# Digital_Output.net
KiCad netlist of a schematic drawn in Altium Designer
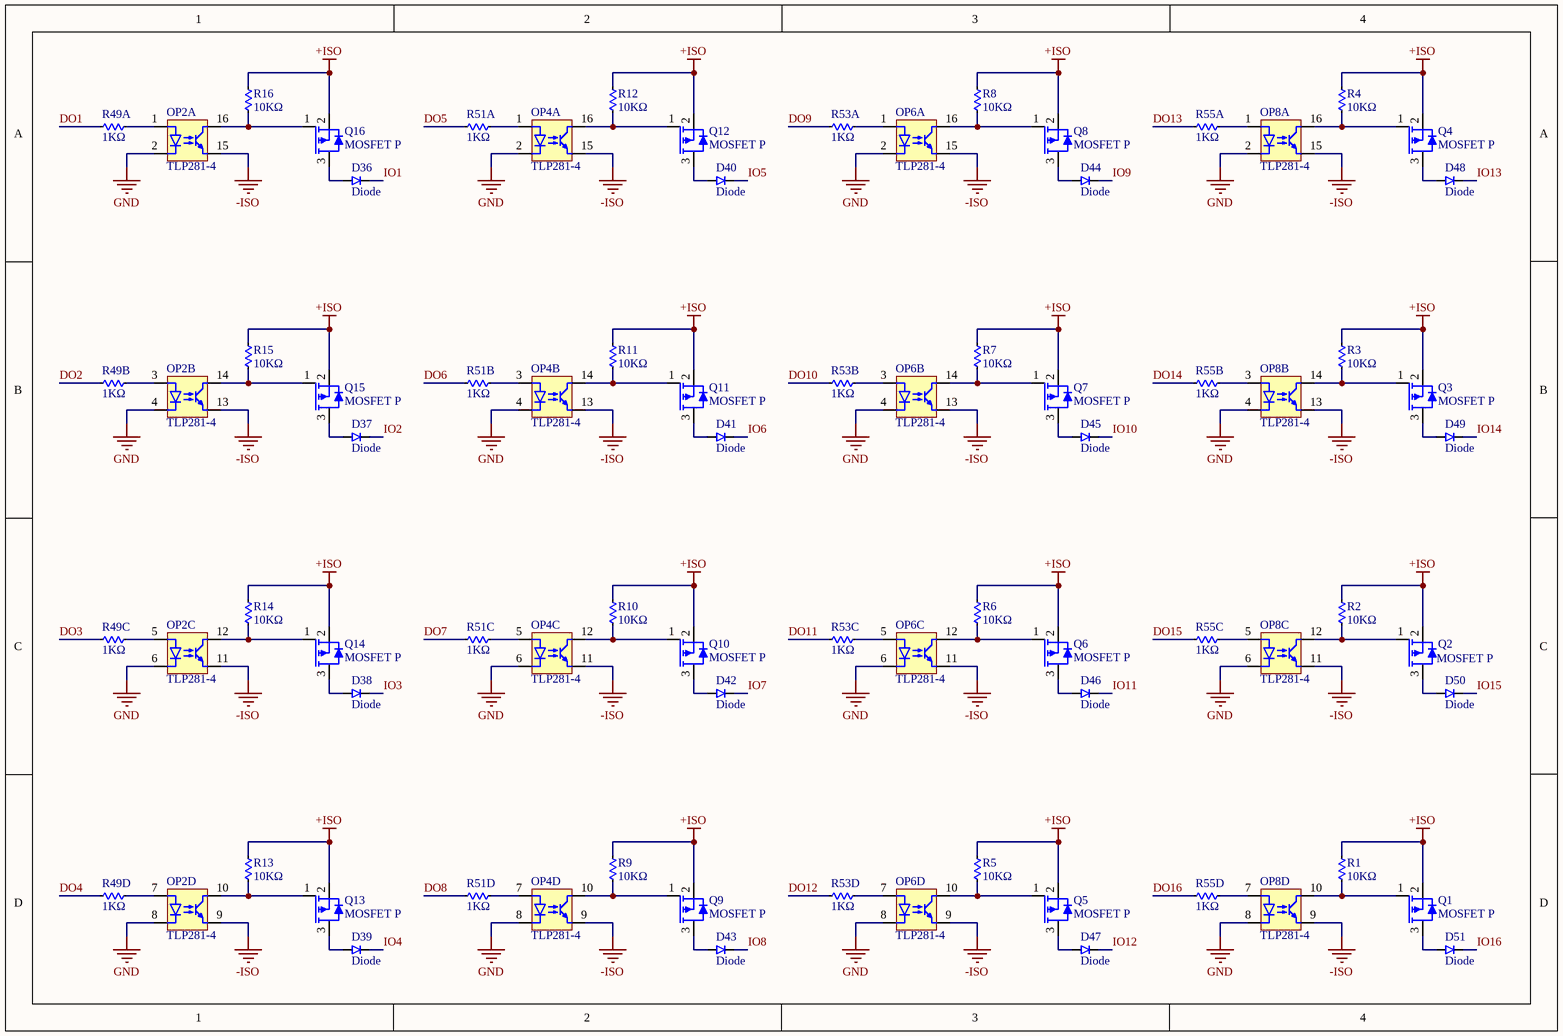
[diagram p0: Digital Output.SchDoc]

(export (version "E")
  (design (tool "Eeschema 10.0.6"))
  (components
    (comp (ref "D36") (value "Diode") (footprint "DIOMELF3515L") (libsource (lib "Shahnahad") (part "Diode")))
    (comp (ref "D37") (value "Diode") (footprint "DIOMELF3515L") (libsource (lib "Shahnahad") (part "Diode")))
    (comp (ref "D38") (value "Diode") (footprint "DIOMELF3515L") (libsource (lib "Shahnahad") (part "Diode")))
    (comp (ref "D39") (value "Diode") (footprint "DIOMELF3515L") (libsource (lib "Shahnahad") (part "Diode")))
    (comp (ref "D40") (value "Diode") (footprint "DIOMELF3515L") (libsource (lib "Shahnahad") (part "Diode")))
    (comp (ref "D41") (value "Diode") (footprint "DIOMELF3515L") (libsource (lib "Shahnahad") (part "Diode")))
    (comp (ref "D42") (value "Diode") (footprint "DIOMELF3515L") (libsource (lib "Shahnahad") (part "Diode")))
    (comp (ref "D43") (value "Diode") (footprint "DIOMELF3515L") (libsource (lib "Shahnahad") (part "Diode")))
    (comp (ref "D44") (value "Diode") (footprint "DIOMELF3515L") (libsource (lib "Shahnahad") (part "Diode")))
    (comp (ref "D45") (value "Diode") (footprint "DIOMELF3515L") (libsource (lib "Shahnahad") (part "Diode")))
    (comp (ref "D46") (value "Diode") (footprint "DIOMELF3515L") (libsource (lib "Shahnahad") (part "Diode")))
    (comp (ref "D47") (value "Diode") (footprint "DIOMELF3515L") (libsource (lib "Shahnahad") (part "Diode")))
    (comp (ref "D48") (value "Diode") (footprint "DIOMELF3515L") (libsource (lib "Shahnahad") (part "Diode")))
    (comp (ref "D49") (value "Diode") (footprint "DIOMELF3515L") (libsource (lib "Shahnahad") (part "Diode")))
    (comp (ref "D50") (value "Diode") (footprint "DIOMELF3515L") (libsource (lib "Shahnahad") (part "Diode")))
    (comp (ref "D51") (value "Diode") (footprint "DIOMELF3515L") (libsource (lib "Shahnahad") (part "Diode")))
    (comp (ref "OP2")
      (value "TLP281-4")
      (footprint "SO16 TOSHIBA OPTOCOUPLER")
      (libsource (lib "Shahnahad") (part "TLP281-4"))
    )
    (comp (ref "OP4")
      (value "TLP281-4")
      (footprint "SO16 TOSHIBA OPTOCOUPLER")
      (libsource (lib "Shahnahad") (part "TLP281-4"))
    )
    (comp (ref "OP6")
      (value "TLP281-4")
      (footprint "SO16 TOSHIBA OPTOCOUPLER")
      (libsource (lib "Shahnahad") (part "TLP281-4"))
    )
    (comp (ref "OP8")
      (value "TLP281-4")
      (footprint "SO16 TOSHIBA OPTOCOUPLER")
      (libsource (lib "Shahnahad") (part "TLP281-4"))
    )
    (comp (ref "Q1") (value "MOSFET P") (footprint "SOT23") (libsource (lib "Shahnahad") (part "MOSFET P")))
    (comp (ref "Q2") (value "MOSFET P") (footprint "SOT23") (libsource (lib "Shahnahad") (part "MOSFET P")))
    (comp (ref "Q3") (value "MOSFET P") (footprint "SOT23") (libsource (lib "Shahnahad") (part "MOSFET P")))
    (comp (ref "Q4") (value "MOSFET P") (footprint "SOT23") (libsource (lib "Shahnahad") (part "MOSFET P")))
    (comp (ref "Q5") (value "MOSFET P") (footprint "SOT23") (libsource (lib "Shahnahad") (part "MOSFET P")))
    (comp (ref "Q6") (value "MOSFET P") (footprint "SOT23") (libsource (lib "Shahnahad") (part "MOSFET P")))
    (comp (ref "Q7") (value "MOSFET P") (footprint "SOT23") (libsource (lib "Shahnahad") (part "MOSFET P")))
    (comp (ref "Q8") (value "MOSFET P") (footprint "SOT23") (libsource (lib "Shahnahad") (part "MOSFET P")))
    (comp (ref "Q9") (value "MOSFET P") (footprint "SOT23") (libsource (lib "Shahnahad") (part "MOSFET P")))
    (comp (ref "Q10") (value "MOSFET P") (footprint "SOT23") (libsource (lib "Shahnahad") (part "MOSFET P")))
    (comp (ref "Q11") (value "MOSFET P") (footprint "SOT23") (libsource (lib "Shahnahad") (part "MOSFET P")))
    (comp (ref "Q12") (value "MOSFET P") (footprint "SOT23") (libsource (lib "Shahnahad") (part "MOSFET P")))
    (comp (ref "Q13") (value "MOSFET P") (footprint "SOT23") (libsource (lib "Shahnahad") (part "MOSFET P")))
    (comp (ref "Q14") (value "MOSFET P") (footprint "SOT23") (libsource (lib "Shahnahad") (part "MOSFET P")))
    (comp (ref "Q15") (value "MOSFET P") (footprint "SOT23") (libsource (lib "Shahnahad") (part "MOSFET P")))
    (comp (ref "Q16") (value "MOSFET P") (footprint "SOT23") (libsource (lib "Shahnahad") (part "MOSFET P")))
    (comp (ref "R1") (value "10KΩ") (footprint "RES 0603 10K") (libsource (lib "Shahnahad") (part "RES 10K")))
    (comp (ref "R2") (value "10KΩ") (footprint "RES 0603 10K") (libsource (lib "Shahnahad") (part "RES 10K")))
    (comp (ref "R3") (value "10KΩ") (footprint "RES 0603 10K") (libsource (lib "Shahnahad") (part "RES 10K")))
    (comp (ref "R4") (value "10KΩ") (footprint "RES 0603 10K") (libsource (lib "Shahnahad") (part "RES 10K")))
    (comp (ref "R5") (value "10KΩ") (footprint "RES 0603 10K") (libsource (lib "Shahnahad") (part "RES 10K")))
    (comp (ref "R6") (value "10KΩ") (footprint "RES 0603 10K") (libsource (lib "Shahnahad") (part "RES 10K")))
    (comp (ref "R7") (value "10KΩ") (footprint "RES 0603 10K") (libsource (lib "Shahnahad") (part "RES 10K")))
    (comp (ref "R8") (value "10KΩ") (footprint "RES 0603 10K") (libsource (lib "Shahnahad") (part "RES 10K")))
    (comp (ref "R9") (value "10KΩ") (footprint "RES 0603 10K") (libsource (lib "Shahnahad") (part "RES 10K")))
    (comp (ref "R10")
      (value "10KΩ")
      (footprint "RES 0603 10K")
      (libsource (lib "Shahnahad") (part "RES 10K"))
    )
    (comp (ref "R11")
      (value "10KΩ")
      (footprint "RES 0603 10K")
      (libsource (lib "Shahnahad") (part "RES 10K"))
    )
    (comp (ref "R12")
      (value "10KΩ")
      (footprint "RES 0603 10K")
      (libsource (lib "Shahnahad") (part "RES 10K"))
    )
    (comp (ref "R13")
      (value "10KΩ")
      (footprint "RES 0603 10K")
      (libsource (lib "Shahnahad") (part "RES 10K"))
    )
    (comp (ref "R14")
      (value "10KΩ")
      (footprint "RES 0603 10K")
      (libsource (lib "Shahnahad") (part "RES 10K"))
    )
    (comp (ref "R15")
      (value "10KΩ")
      (footprint "RES 0603 10K")
      (libsource (lib "Shahnahad") (part "RES 10K"))
    )
    (comp (ref "R16")
      (value "10KΩ")
      (footprint "RES 0603 10K")
      (libsource (lib "Shahnahad") (part "RES 10K"))
    )
    (comp (ref "R49")
      (value "1KΩ")
      (footprint "RES ARRAY 4X0603 1K")
      (libsource (lib "Shahnahad") (part "RES ARRAY 1K"))
    )
    (comp (ref "R51")
      (value "1KΩ")
      (footprint "RES ARRAY 4X0603 1K")
      (libsource (lib "Shahnahad") (part "RES ARRAY 1K"))
    )
    (comp (ref "R53")
      (value "1KΩ")
      (footprint "RES ARRAY 4X0603 1K")
      (libsource (lib "Shahnahad") (part "RES ARRAY 1K"))
    )
    (comp (ref "R55")
      (value "1KΩ")
      (footprint "RES ARRAY 4X0603 1K")
      (libsource (lib "Shahnahad") (part "RES ARRAY 1K"))
    )
  )
  (nets
    (net (code "1") (name "+ISO") (class "Default")
      (node (ref "Q1") (pin "2") (pinfunction "S_2") (pintype "passive"))
      (node (ref "Q10") (pin "2") (pinfunction "S_2") (pintype "passive"))
      (node (ref "Q11") (pin "2") (pinfunction "S_2") (pintype "passive"))
      (node (ref "Q12") (pin "2") (pinfunction "S_2") (pintype "passive"))
      (node (ref "Q13") (pin "2") (pinfunction "S_2") (pintype "passive"))
      (node (ref "Q14") (pin "2") (pinfunction "S_2") (pintype "passive"))
      (node (ref "Q15") (pin "2") (pinfunction "S_2") (pintype "passive"))
      (node (ref "Q16") (pin "2") (pinfunction "S_2") (pintype "passive"))
      (node (ref "Q2") (pin "2") (pinfunction "S_2") (pintype "passive"))
      (node (ref "Q3") (pin "2") (pinfunction "S_2") (pintype "passive"))
      (node (ref "Q4") (pin "2") (pinfunction "S_2") (pintype "passive"))
      (node (ref "Q5") (pin "2") (pinfunction "S_2") (pintype "passive"))
      (node (ref "Q6") (pin "2") (pinfunction "S_2") (pintype "passive"))
      (node (ref "Q7") (pin "2") (pinfunction "S_2") (pintype "passive"))
      (node (ref "Q8") (pin "2") (pinfunction "S_2") (pintype "passive"))
      (node (ref "Q9") (pin "2") (pinfunction "S_2") (pintype "passive"))
      (node (ref "R1") (pin "2") (pintype "passive"))
      (node (ref "R10") (pin "2") (pintype "passive"))
      (node (ref "R11") (pin "2") (pintype "passive"))
      (node (ref "R12") (pin "2") (pintype "passive"))
      (node (ref "R13") (pin "2") (pintype "passive"))
      (node (ref "R14") (pin "2") (pintype "passive"))
      (node (ref "R15") (pin "2") (pintype "passive"))
      (node (ref "R16") (pin "2") (pintype "passive"))
      (node (ref "R2") (pin "2") (pintype "passive"))
      (node (ref "R3") (pin "2") (pintype "passive"))
      (node (ref "R4") (pin "2") (pintype "passive"))
      (node (ref "R5") (pin "2") (pintype "passive"))
      (node (ref "R6") (pin "2") (pintype "passive"))
      (node (ref "R7") (pin "2") (pintype "passive"))
      (node (ref "R8") (pin "2") (pintype "passive"))
      (node (ref "R9") (pin "2") (pintype "passive"))
    )
    (net (code "2") (name "-ISO") (class "Default")
      (node (ref "OP2") (pin "11") (pinfunction "11_11") (pintype "passive"))
      (node (ref "OP2") (pin "13") (pinfunction "13_13") (pintype "passive"))
      (node (ref "OP2") (pin "15") (pinfunction "15_15") (pintype "passive"))
      (node (ref "OP2") (pin "9") (pinfunction "9_9") (pintype "passive"))
      (node (ref "OP4") (pin "11") (pinfunction "11_11") (pintype "passive"))
      (node (ref "OP4") (pin "13") (pinfunction "13_13") (pintype "passive"))
      (node (ref "OP4") (pin "15") (pinfunction "15_15") (pintype "passive"))
      (node (ref "OP4") (pin "9") (pinfunction "9_9") (pintype "passive"))
      (node (ref "OP6") (pin "11") (pinfunction "11_11") (pintype "passive"))
      (node (ref "OP6") (pin "13") (pinfunction "13_13") (pintype "passive"))
      (node (ref "OP6") (pin "15") (pinfunction "15_15") (pintype "passive"))
      (node (ref "OP6") (pin "9") (pinfunction "9_9") (pintype "passive"))
      (node (ref "OP8") (pin "11") (pinfunction "11_11") (pintype "passive"))
      (node (ref "OP8") (pin "13") (pinfunction "13_13") (pintype "passive"))
      (node (ref "OP8") (pin "15") (pinfunction "15_15") (pintype "passive"))
      (node (ref "OP8") (pin "9") (pinfunction "9_9") (pintype "passive"))
    )
    (net (code "3") (name "/DO1") (class "Default") (node (ref "R49") (pin "1") (pintype "passive")))
    (net (code "4") (name "/DO2") (class "Default") (node (ref "R49") (pin "2") (pintype "passive")))
    (net (code "5") (name "/DO3") (class "Default") (node (ref "R49") (pin "3") (pintype "passive")))
    (net (code "6") (name "/DO4") (class "Default") (node (ref "R49") (pin "4") (pintype "passive")))
    (net (code "7") (name "/DO5") (class "Default") (node (ref "R51") (pin "1") (pintype "passive")))
    (net (code "8") (name "/DO6") (class "Default") (node (ref "R51") (pin "2") (pintype "passive")))
    (net (code "9") (name "/DO7") (class "Default") (node (ref "R51") (pin "3") (pintype "passive")))
    (net (code "10") (name "/DO8") (class "Default") (node (ref "R51") (pin "4") (pintype "passive")))
    (net (code "11") (name "/DO9") (class "Default") (node (ref "R53") (pin "1") (pintype "passive")))
    (net (code "12") (name "/DO10") (class "Default") (node (ref "R53") (pin "2") (pintype "passive")))
    (net (code "13") (name "/DO11") (class "Default") (node (ref "R53") (pin "3") (pintype "passive")))
    (net (code "14") (name "/DO12") (class "Default") (node (ref "R53") (pin "4") (pintype "passive")))
    (net (code "15") (name "/DO13") (class "Default") (node (ref "R55") (pin "1") (pintype "passive")))
    (net (code "16") (name "/DO14") (class "Default") (node (ref "R55") (pin "2") (pintype "passive")))
    (net (code "17") (name "/DO15") (class "Default") (node (ref "R55") (pin "3") (pintype "passive")))
    (net (code "18") (name "/DO16") (class "Default") (node (ref "R55") (pin "4") (pintype "passive")))
    (net (code "19") (name "/IO1") (class "Default") (node (ref "D36") (pin "1") (pintype "passive")))
    (net (code "20") (name "/IO2") (class "Default") (node (ref "D37") (pin "1") (pintype "passive")))
    (net (code "21") (name "/IO3") (class "Default") (node (ref "D38") (pin "1") (pintype "passive")))
    (net (code "22") (name "/IO4") (class "Default") (node (ref "D39") (pin "1") (pintype "passive")))
    (net (code "23") (name "/IO5") (class "Default") (node (ref "D40") (pin "1") (pintype "passive")))
    (net (code "24") (name "/IO6") (class "Default") (node (ref "D41") (pin "1") (pintype "passive")))
    (net (code "25") (name "/IO7") (class "Default") (node (ref "D42") (pin "1") (pintype "passive")))
    (net (code "26") (name "/IO8") (class "Default") (node (ref "D43") (pin "1") (pintype "passive")))
    (net (code "27") (name "/IO9") (class "Default") (node (ref "D44") (pin "1") (pintype "passive")))
    (net (code "28") (name "/IO10") (class "Default") (node (ref "D45") (pin "1") (pintype "passive")))
    (net (code "29") (name "/IO11") (class "Default") (node (ref "D46") (pin "1") (pintype "passive")))
    (net (code "30") (name "/IO12") (class "Default") (node (ref "D47") (pin "1") (pintype "passive")))
    (net (code "31") (name "/IO13") (class "Default") (node (ref "D48") (pin "1") (pintype "passive")))
    (net (code "32") (name "/IO14") (class "Default") (node (ref "D49") (pin "1") (pintype "passive")))
    (net (code "33") (name "/IO15") (class "Default") (node (ref "D50") (pin "1") (pintype "passive")))
    (net (code "34") (name "/IO16") (class "Default") (node (ref "D51") (pin "1") (pintype "passive")))
    (net (code "35") (name "GND") (class "Default")
      (node (ref "OP2") (pin "2") (pinfunction "2_2") (pintype "passive"))
      (node (ref "OP2") (pin "4") (pinfunction "4_4") (pintype "passive"))
      (node (ref "OP2") (pin "6") (pinfunction "6_6") (pintype "passive"))
      (node (ref "OP2") (pin "8") (pinfunction "8_8") (pintype "passive"))
      (node (ref "OP4") (pin "2") (pinfunction "2_2") (pintype "passive"))
      (node (ref "OP4") (pin "4") (pinfunction "4_4") (pintype "passive"))
      (node (ref "OP4") (pin "6") (pinfunction "6_6") (pintype "passive"))
      (node (ref "OP4") (pin "8") (pinfunction "8_8") (pintype "passive"))
      (node (ref "OP6") (pin "2") (pinfunction "2_2") (pintype "passive"))
      (node (ref "OP6") (pin "4") (pinfunction "4_4") (pintype "passive"))
      (node (ref "OP6") (pin "6") (pinfunction "6_6") (pintype "passive"))
      (node (ref "OP6") (pin "8") (pinfunction "8_8") (pintype "passive"))
      (node (ref "OP8") (pin "2") (pinfunction "2_2") (pintype "passive"))
      (node (ref "OP8") (pin "4") (pinfunction "4_4") (pintype "passive"))
      (node (ref "OP8") (pin "6") (pinfunction "6_6") (pintype "passive"))
      (node (ref "OP8") (pin "8") (pinfunction "8_8") (pintype "passive"))
    )
    (net (code "36") (name "Net-(OP2-Pad1)") (class "Default")
      (node (ref "OP2") (pin "1") (pinfunction "1_1") (pintype "passive"))
      (node (ref "R49") (pin "8") (pintype "passive"))
    )
    (net (code "37") (name "Net-(OP2-Pad3)") (class "Default")
      (node (ref "OP2") (pin "3") (pinfunction "3_3") (pintype "passive"))
      (node (ref "R49") (pin "7") (pintype "passive"))
    )
    (net (code "38") (name "Net-(OP2-Pad5)") (class "Default")
      (node (ref "OP2") (pin "5") (pinfunction "5_5") (pintype "passive"))
      (node (ref "R49") (pin "6") (pintype "passive"))
    )
    (net (code "39") (name "Net-(OP2-Pad7)") (class "Default")
      (node (ref "OP2") (pin "7") (pinfunction "7_7") (pintype "passive"))
      (node (ref "R49") (pin "5") (pintype "passive"))
    )
    (net (code "40") (name "Net-(OP4-Pad1)") (class "Default")
      (node (ref "OP4") (pin "1") (pinfunction "1_1") (pintype "passive"))
      (node (ref "R51") (pin "8") (pintype "passive"))
    )
    (net (code "41") (name "Net-(OP4-Pad3)") (class "Default")
      (node (ref "OP4") (pin "3") (pinfunction "3_3") (pintype "passive"))
      (node (ref "R51") (pin "7") (pintype "passive"))
    )
    (net (code "42") (name "Net-(OP4-Pad5)") (class "Default")
      (node (ref "OP4") (pin "5") (pinfunction "5_5") (pintype "passive"))
      (node (ref "R51") (pin "6") (pintype "passive"))
    )
    (net (code "43") (name "Net-(OP4-Pad7)") (class "Default")
      (node (ref "OP4") (pin "7") (pinfunction "7_7") (pintype "passive"))
      (node (ref "R51") (pin "5") (pintype "passive"))
    )
    (net (code "44") (name "Net-(OP6-Pad1)") (class "Default")
      (node (ref "OP6") (pin "1") (pinfunction "1_1") (pintype "passive"))
      (node (ref "R53") (pin "8") (pintype "passive"))
    )
    (net (code "45") (name "Net-(OP6-Pad3)") (class "Default")
      (node (ref "OP6") (pin "3") (pinfunction "3_3") (pintype "passive"))
      (node (ref "R53") (pin "7") (pintype "passive"))
    )
    (net (code "46") (name "Net-(OP6-Pad5)") (class "Default")
      (node (ref "OP6") (pin "5") (pinfunction "5_5") (pintype "passive"))
      (node (ref "R53") (pin "6") (pintype "passive"))
    )
    (net (code "47") (name "Net-(OP6-Pad7)") (class "Default")
      (node (ref "OP6") (pin "7") (pinfunction "7_7") (pintype "passive"))
      (node (ref "R53") (pin "5") (pintype "passive"))
    )
    (net (code "48") (name "Net-(OP8-Pad1)") (class "Default")
      (node (ref "OP8") (pin "1") (pinfunction "1_1") (pintype "passive"))
      (node (ref "R55") (pin "8") (pintype "passive"))
    )
    (net (code "49") (name "Net-(OP8-Pad3)") (class "Default")
      (node (ref "OP8") (pin "3") (pinfunction "3_3") (pintype "passive"))
      (node (ref "R55") (pin "7") (pintype "passive"))
    )
    (net (code "50") (name "Net-(OP8-Pad5)") (class "Default")
      (node (ref "OP8") (pin "5") (pinfunction "5_5") (pintype "passive"))
      (node (ref "R55") (pin "6") (pintype "passive"))
    )
    (net (code "51") (name "Net-(OP8-Pad7)") (class "Default")
      (node (ref "OP8") (pin "7") (pinfunction "7_7") (pintype "passive"))
      (node (ref "R55") (pin "5") (pintype "passive"))
    )
    (net (code "52") (name "Net-(Q1-D)") (class "Default")
      (node (ref "D51") (pin "2") (pintype "passive"))
      (node (ref "Q1") (pin "3") (pinfunction "D_3") (pintype "passive"))
    )
    (net (code "53") (name "Net-(Q1-G)") (class "Default")
      (node (ref "OP8") (pin "10") (pinfunction "10_10") (pintype "passive"))
      (node (ref "Q1") (pin "1") (pinfunction "G_1") (pintype "passive"))
      (node (ref "R1") (pin "1") (pintype "passive"))
    )
    (net (code "54") (name "Net-(Q2-D)") (class "Default")
      (node (ref "D50") (pin "2") (pintype "passive"))
      (node (ref "Q2") (pin "3") (pinfunction "D_3") (pintype "passive"))
    )
    (net (code "55") (name "Net-(Q2-G)") (class "Default")
      (node (ref "OP8") (pin "12") (pinfunction "12_12") (pintype "passive"))
      (node (ref "Q2") (pin "1") (pinfunction "G_1") (pintype "passive"))
      (node (ref "R2") (pin "1") (pintype "passive"))
    )
    (net (code "56") (name "Net-(Q3-D)") (class "Default")
      (node (ref "D49") (pin "2") (pintype "passive"))
      (node (ref "Q3") (pin "3") (pinfunction "D_3") (pintype "passive"))
    )
    (net (code "57") (name "Net-(Q3-G)") (class "Default")
      (node (ref "OP8") (pin "14") (pinfunction "14_14") (pintype "passive"))
      (node (ref "Q3") (pin "1") (pinfunction "G_1") (pintype "passive"))
      (node (ref "R3") (pin "1") (pintype "passive"))
    )
    (net (code "58") (name "Net-(Q4-D)") (class "Default")
      (node (ref "D48") (pin "2") (pintype "passive"))
      (node (ref "Q4") (pin "3") (pinfunction "D_3") (pintype "passive"))
    )
    (net (code "59") (name "Net-(Q4-G)") (class "Default")
      (node (ref "OP8") (pin "16") (pinfunction "16_16") (pintype "passive"))
      (node (ref "Q4") (pin "1") (pinfunction "G_1") (pintype "passive"))
      (node (ref "R4") (pin "1") (pintype "passive"))
    )
    (net (code "60") (name "Net-(Q5-D)") (class "Default")
      (node (ref "D47") (pin "2") (pintype "passive"))
      (node (ref "Q5") (pin "3") (pinfunction "D_3") (pintype "passive"))
    )
    (net (code "61") (name "Net-(Q5-G)") (class "Default")
      (node (ref "OP6") (pin "10") (pinfunction "10_10") (pintype "passive"))
      (node (ref "Q5") (pin "1") (pinfunction "G_1") (pintype "passive"))
      (node (ref "R5") (pin "1") (pintype "passive"))
    )
    (net (code "62") (name "Net-(Q6-D)") (class "Default")
      (node (ref "D46") (pin "2") (pintype "passive"))
      (node (ref "Q6") (pin "3") (pinfunction "D_3") (pintype "passive"))
    )
    (net (code "63") (name "Net-(Q6-G)") (class "Default")
      (node (ref "OP6") (pin "12") (pinfunction "12_12") (pintype "passive"))
      (node (ref "Q6") (pin "1") (pinfunction "G_1") (pintype "passive"))
      (node (ref "R6") (pin "1") (pintype "passive"))
    )
    (net (code "64") (name "Net-(Q7-D)") (class "Default")
      (node (ref "D45") (pin "2") (pintype "passive"))
      (node (ref "Q7") (pin "3") (pinfunction "D_3") (pintype "passive"))
    )
    (net (code "65") (name "Net-(Q7-G)") (class "Default")
      (node (ref "OP6") (pin "14") (pinfunction "14_14") (pintype "passive"))
      (node (ref "Q7") (pin "1") (pinfunction "G_1") (pintype "passive"))
      (node (ref "R7") (pin "1") (pintype "passive"))
    )
    (net (code "66") (name "Net-(Q8-D)") (class "Default")
      (node (ref "D44") (pin "2") (pintype "passive"))
      (node (ref "Q8") (pin "3") (pinfunction "D_3") (pintype "passive"))
    )
    (net (code "67") (name "Net-(Q8-G)") (class "Default")
      (node (ref "OP6") (pin "16") (pinfunction "16_16") (pintype "passive"))
      (node (ref "Q8") (pin "1") (pinfunction "G_1") (pintype "passive"))
      (node (ref "R8") (pin "1") (pintype "passive"))
    )
    (net (code "68") (name "Net-(Q9-D)") (class "Default")
      (node (ref "D43") (pin "2") (pintype "passive"))
      (node (ref "Q9") (pin "3") (pinfunction "D_3") (pintype "passive"))
    )
    (net (code "69") (name "Net-(Q9-G)") (class "Default")
      (node (ref "OP4") (pin "10") (pinfunction "10_10") (pintype "passive"))
      (node (ref "Q9") (pin "1") (pinfunction "G_1") (pintype "passive"))
      (node (ref "R9") (pin "1") (pintype "passive"))
    )
    (net (code "70") (name "Net-(Q10-D)") (class "Default")
      (node (ref "D42") (pin "2") (pintype "passive"))
      (node (ref "Q10") (pin "3") (pinfunction "D_3") (pintype "passive"))
    )
    (net (code "71") (name "Net-(Q10-G)") (class "Default")
      (node (ref "OP4") (pin "12") (pinfunction "12_12") (pintype "passive"))
      (node (ref "Q10") (pin "1") (pinfunction "G_1") (pintype "passive"))
      (node (ref "R10") (pin "1") (pintype "passive"))
    )
    (net (code "72") (name "Net-(Q11-D)") (class "Default")
      (node (ref "D41") (pin "2") (pintype "passive"))
      (node (ref "Q11") (pin "3") (pinfunction "D_3") (pintype "passive"))
    )
    (net (code "73") (name "Net-(Q11-G)") (class "Default")
      (node (ref "OP4") (pin "14") (pinfunction "14_14") (pintype "passive"))
      (node (ref "Q11") (pin "1") (pinfunction "G_1") (pintype "passive"))
      (node (ref "R11") (pin "1") (pintype "passive"))
    )
    (net (code "74") (name "Net-(Q12-D)") (class "Default")
      (node (ref "D40") (pin "2") (pintype "passive"))
      (node (ref "Q12") (pin "3") (pinfunction "D_3") (pintype "passive"))
    )
    (net (code "75") (name "Net-(Q12-G)") (class "Default")
      (node (ref "OP4") (pin "16") (pinfunction "16_16") (pintype "passive"))
      (node (ref "Q12") (pin "1") (pinfunction "G_1") (pintype "passive"))
      (node (ref "R12") (pin "1") (pintype "passive"))
    )
    (net (code "76") (name "Net-(Q13-D)") (class "Default")
      (node (ref "D39") (pin "2") (pintype "passive"))
      (node (ref "Q13") (pin "3") (pinfunction "D_3") (pintype "passive"))
    )
    (net (code "77") (name "Net-(Q13-G)") (class "Default")
      (node (ref "OP2") (pin "10") (pinfunction "10_10") (pintype "passive"))
      (node (ref "Q13") (pin "1") (pinfunction "G_1") (pintype "passive"))
      (node (ref "R13") (pin "1") (pintype "passive"))
    )
    (net (code "78") (name "Net-(Q14-D)") (class "Default")
      (node (ref "D38") (pin "2") (pintype "passive"))
      (node (ref "Q14") (pin "3") (pinfunction "D_3") (pintype "passive"))
    )
    (net (code "79") (name "Net-(Q14-G)") (class "Default")
      (node (ref "OP2") (pin "12") (pinfunction "12_12") (pintype "passive"))
      (node (ref "Q14") (pin "1") (pinfunction "G_1") (pintype "passive"))
      (node (ref "R14") (pin "1") (pintype "passive"))
    )
    (net (code "80") (name "Net-(Q15-D)") (class "Default")
      (node (ref "D37") (pin "2") (pintype "passive"))
      (node (ref "Q15") (pin "3") (pinfunction "D_3") (pintype "passive"))
    )
    (net (code "81") (name "Net-(Q15-G)") (class "Default")
      (node (ref "OP2") (pin "14") (pinfunction "14_14") (pintype "passive"))
      (node (ref "Q15") (pin "1") (pinfunction "G_1") (pintype "passive"))
      (node (ref "R15") (pin "1") (pintype "passive"))
    )
    (net (code "82") (name "Net-(Q16-D)") (class "Default")
      (node (ref "D36") (pin "2") (pintype "passive"))
      (node (ref "Q16") (pin "3") (pinfunction "D_3") (pintype "passive"))
    )
    (net (code "83") (name "Net-(Q16-G)") (class "Default")
      (node (ref "OP2") (pin "16") (pinfunction "16_16") (pintype "passive"))
      (node (ref "Q16") (pin "1") (pinfunction "G_1") (pintype "passive"))
      (node (ref "R16") (pin "1") (pintype "passive"))
    )
  )
)
